# Sheet1.net
KiCad netlist of a schematic drawn in Altium Designer
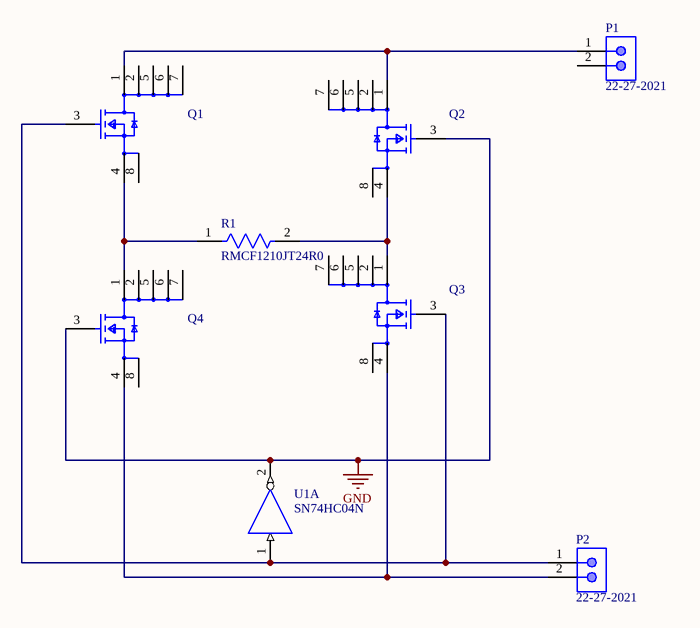
[diagram p0: Sheet1.SchDoc]

(export (version "E")
  (design (tool "Eeschema 10.0.6"))
  (components
    (comp (ref "P1")
      (value "22-27-2021")
      (footprint "PIN")
      (fields (field (name "MANUFACTURER") "Molex") (field (name "PARTNUMBER") "0022272021"))
      (libsource (lib "Schlib1") (part "PIN"))
    )
    (comp (ref "P2")
      (value "22-27-2021")
      (footprint "PIN")
      (fields (field (name "MANUFACTURER") "Molex") (field (name "PARTNUMBER") "0022272021"))
      (libsource (lib "Schlib1") (part "PIN"))
    )
    (comp (ref "Q1")
      (value "IRL60HS118")
      (footprint "NMOS")
      (description "MOSFET N-CH 60V 18.5A 6PQFN")
      (libsource (lib "Schlib1") (part "NMOS"))
    )
    (comp (ref "Q2")
      (value "IRL60HS118")
      (footprint "NMOS")
      (description "MOSFET N-CH 60V 18.5A 6PQFN")
      (libsource (lib "Schlib1") (part "NMOS"))
    )
    (comp (ref "Q3")
      (value "IRL60HS118")
      (footprint "NMOS")
      (description "MOSFET N-CH 60V 18.5A 6PQFN")
      (libsource (lib "Schlib1") (part "NMOS"))
    )
    (comp (ref "Q4")
      (value "IRL60HS118")
      (footprint "NMOS")
      (description "MOSFET N-CH 60V 18.5A 6PQFN")
      (libsource (lib "Schlib1") (part "NMOS"))
    )
    (comp (ref "R1")
      (value "RMCF1210JT24R0")
      (footprint "FP-RMCF1210-IPC_B")
      (description "24Ω ±5% 0.5W 1210 Thick Film Chip Resistor AEC-Q200 compliant")
      (fields (field (name "TOLERANCE") "5%"))
      (libsource (lib "Schlib1") (part "RESISTOR"))
    )
    (comp (ref "U1")
      (value "SN74HC04N")
      (footprint "NOT")
      (description "Hex Inverters, N0014A, TUBE")
      (fields
        (field (name "MANUFACTURER") "Texas Instruments")
        (field (name "GENERIC PART NUMBER") "SN74HC04")
      )
      (libsource (lib "Schlib1") (part "NOT"))
    )
  )
  (nets
    (net (code "1") (name "GND") (class "Default")
      (node (ref "Q2") (pin "3") (pinfunction "G_3") (pintype "passive"))
      (node (ref "Q4") (pin "3") (pinfunction "G_3") (pintype "passive"))
      (node (ref "U1") (pin "2") (pinfunction "~{1Y}_2") (pintype "output"))
    )
    (net (code "2") (name "Net-(P1-Pad1)") (class "Default")
      (node (ref "P1") (pin "1") (pinfunction "1_1") (pintype "passive"))
      (node (ref "Q1") (pin "1") (pinfunction "D_1") (pintype "passive"))
      (node (ref "Q2") (pin "1") (pinfunction "D_1") (pintype "passive"))
    )
    (net (code "3") (name "Net-(P2-Pad2)") (class "Default")
      (node (ref "P2") (pin "2") (pinfunction "2_2") (pintype "passive"))
      (node (ref "Q3") (pin "4") (pinfunction "S_4") (pintype "passive"))
      (node (ref "Q4") (pin "4") (pinfunction "S_4") (pintype "passive"))
    )
    (net (code "4") (name "Net-(Q1-G)") (class "Default")
      (node (ref "P2") (pin "1") (pinfunction "1_1") (pintype "passive"))
      (node (ref "Q1") (pin "3") (pinfunction "G_3") (pintype "passive"))
      (node (ref "Q3") (pin "3") (pinfunction "G_3") (pintype "passive"))
      (node (ref "U1") (pin "1") (pinfunction "1A_1") (pintype "input"))
    )
    (net (code "5") (name "Net-(Q1-S-Pad4)") (class "Default")
      (node (ref "Q1") (pin "4") (pinfunction "S_4") (pintype "passive"))
      (node (ref "Q4") (pin "1") (pinfunction "D_1") (pintype "passive"))
      (node (ref "R1") (pin "1") (pinfunction "1_1") (pintype "passive"))
    )
    (net (code "6") (name "Net-(Q2-S-Pad4)") (class "Default")
      (node (ref "Q2") (pin "4") (pinfunction "S_4") (pintype "passive"))
      (node (ref "Q3") (pin "1") (pinfunction "D_1") (pintype "passive"))
      (node (ref "R1") (pin "2") (pinfunction "2_2") (pintype "passive"))
    )
    (net (code "7") (name "unconnected-(P1-Pad2)") (class "Default")
      (node (ref "P1") (pin "2") (pinfunction "2_2") (pintype "passive"))
    )
    (net (code "8") (name "unconnected-(Q1-D-Pad2)") (class "Default")
      (node (ref "Q1") (pin "2") (pinfunction "D_2") (pintype "passive"))
    )
    (net (code "9") (name "unconnected-(Q1-D-Pad5)") (class "Default")
      (node (ref "Q1") (pin "5") (pinfunction "D_5") (pintype "passive"))
    )
    (net (code "10") (name "unconnected-(Q1-D-Pad6)") (class "Default")
      (node (ref "Q1") (pin "6") (pinfunction "D_6") (pintype "passive"))
    )
    (net (code "11") (name "unconnected-(Q1-D-Pad7)") (class "Default")
      (node (ref "Q1") (pin "7") (pinfunction "D_7") (pintype "passive"))
    )
    (net (code "12") (name "unconnected-(Q1-S-Pad8)") (class "Default")
      (node (ref "Q1") (pin "8") (pinfunction "S_8") (pintype "passive"))
    )
    (net (code "13") (name "unconnected-(Q2-D-Pad2)") (class "Default")
      (node (ref "Q2") (pin "2") (pinfunction "D_2") (pintype "passive"))
    )
    (net (code "14") (name "unconnected-(Q2-D-Pad5)") (class "Default")
      (node (ref "Q2") (pin "5") (pinfunction "D_5") (pintype "passive"))
    )
    (net (code "15") (name "unconnected-(Q2-D-Pad6)") (class "Default")
      (node (ref "Q2") (pin "6") (pinfunction "D_6") (pintype "passive"))
    )
    (net (code "16") (name "unconnected-(Q2-D-Pad7)") (class "Default")
      (node (ref "Q2") (pin "7") (pinfunction "D_7") (pintype "passive"))
    )
    (net (code "17") (name "unconnected-(Q2-S-Pad8)") (class "Default")
      (node (ref "Q2") (pin "8") (pinfunction "S_8") (pintype "passive"))
    )
    (net (code "18") (name "unconnected-(Q3-D-Pad2)") (class "Default")
      (node (ref "Q3") (pin "2") (pinfunction "D_2") (pintype "passive"))
    )
    (net (code "19") (name "unconnected-(Q3-D-Pad5)") (class "Default")
      (node (ref "Q3") (pin "5") (pinfunction "D_5") (pintype "passive"))
    )
    (net (code "20") (name "unconnected-(Q3-D-Pad6)") (class "Default")
      (node (ref "Q3") (pin "6") (pinfunction "D_6") (pintype "passive"))
    )
    (net (code "21") (name "unconnected-(Q3-D-Pad7)") (class "Default")
      (node (ref "Q3") (pin "7") (pinfunction "D_7") (pintype "passive"))
    )
    (net (code "22") (name "unconnected-(Q3-S-Pad8)") (class "Default")
      (node (ref "Q3") (pin "8") (pinfunction "S_8") (pintype "passive"))
    )
    (net (code "23") (name "unconnected-(Q4-D-Pad2)") (class "Default")
      (node (ref "Q4") (pin "2") (pinfunction "D_2") (pintype "passive"))
    )
    (net (code "24") (name "unconnected-(Q4-D-Pad5)") (class "Default")
      (node (ref "Q4") (pin "5") (pinfunction "D_5") (pintype "passive"))
    )
    (net (code "25") (name "unconnected-(Q4-D-Pad6)") (class "Default")
      (node (ref "Q4") (pin "6") (pinfunction "D_6") (pintype "passive"))
    )
    (net (code "26") (name "unconnected-(Q4-D-Pad7)") (class "Default")
      (node (ref "Q4") (pin "7") (pinfunction "D_7") (pintype "passive"))
    )
    (net (code "27") (name "unconnected-(Q4-S-Pad8)") (class "Default")
      (node (ref "Q4") (pin "8") (pinfunction "S_8") (pintype "passive"))
    )
  )
)
